# EV75E52A_R3_4-PIC_USB.net
KiCad netlist of a schematic drawn in Altium Designer
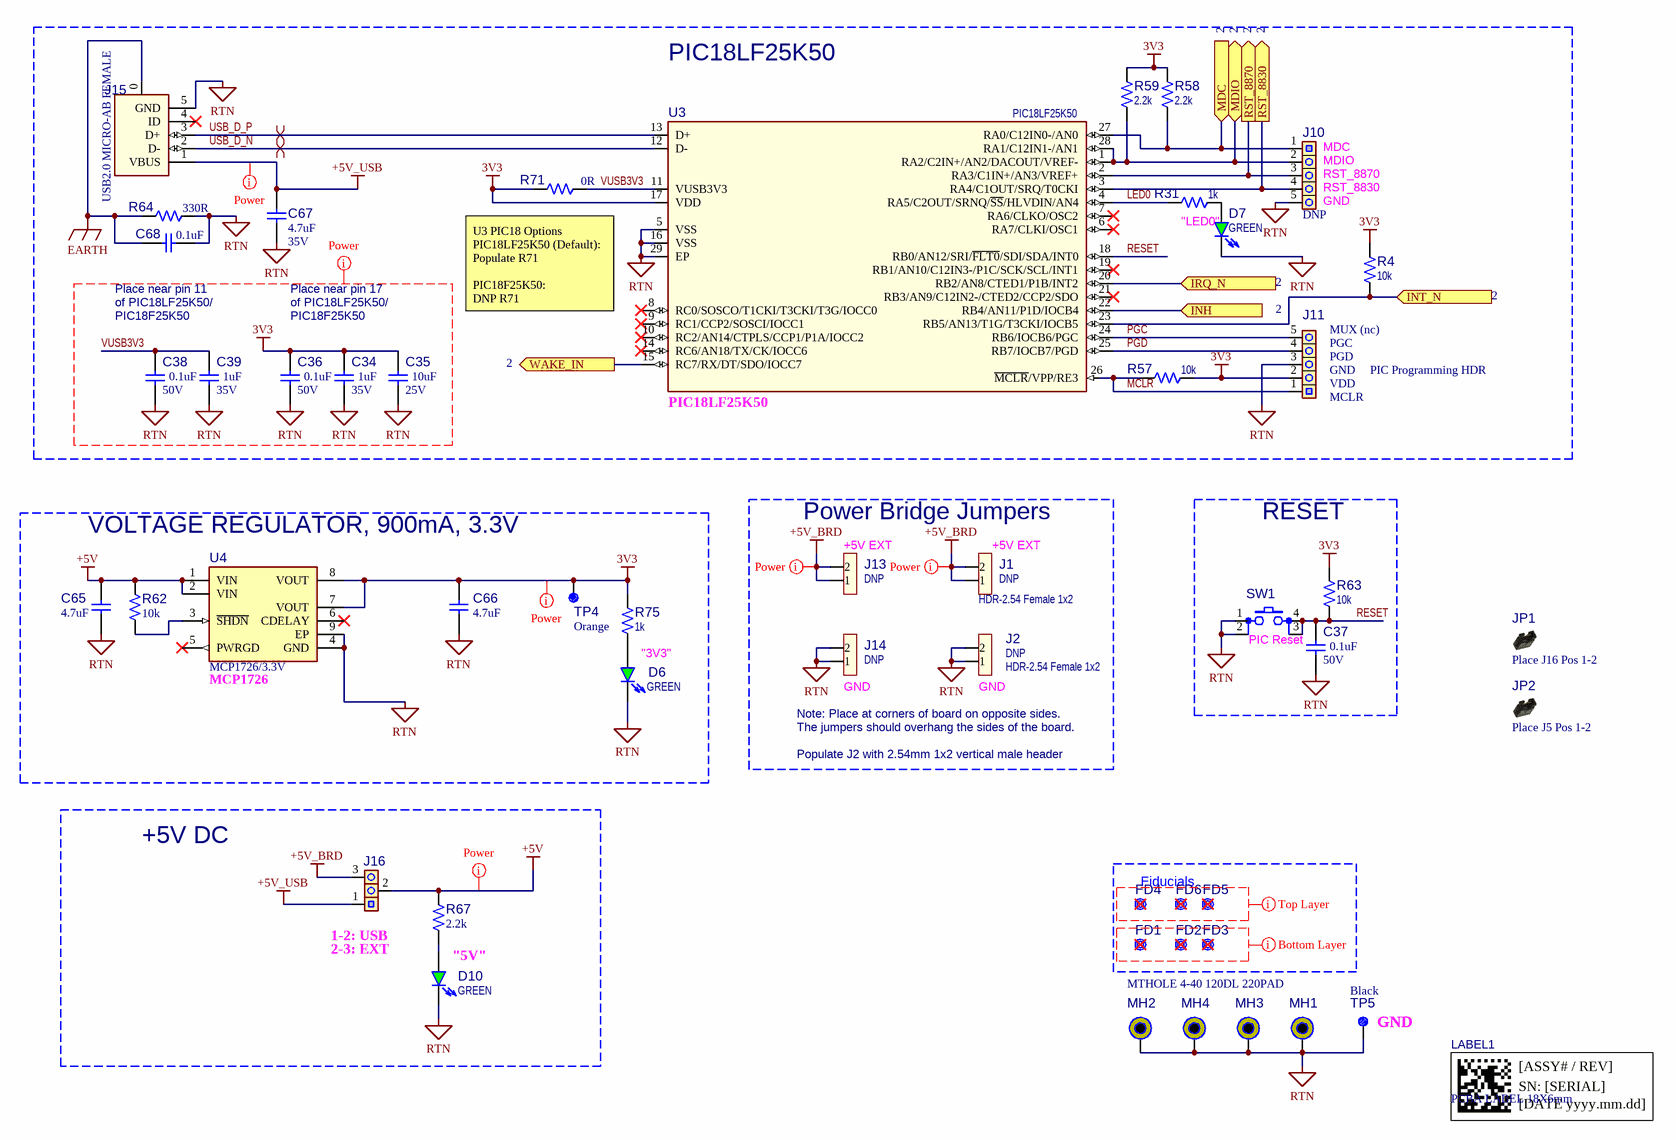
[diagram p0: EV75E52A_R3_4-PIC_USB.SchDoc]

(export (version "E")
  (design (tool "Eeschema 10.0.6"))
  (components
    (comp (ref "C34")
      (value "1uF")
      (footprint "CAP_C_0402")
      (description "Capacitor")
      (fields
        (field (name "VOLTAGE") "35V")
        (field (name "TOLERANCE") "10%")
        (field (name "Comment") "Capacitor NP")
        (field (name "OWNER") "Sam Charles")
      )
      (libsource (lib "MCHP-CDB") (part "Capacitor NP"))
    )
    (comp (ref "C35")
      (value "10uF")
      (footprint "CAP_C_0603")
      (description "Capacitor")
      (fields
        (field (name "VOLTAGE") "25V")
        (field (name "TOLERANCE") "±20%")
        (field (name "Comment") "Capacitor NP")
        (field (name "OWNER") "Tim Moffat")
      )
      (libsource (lib "MCHP-CDB") (part "Capacitor NP"))
    )
    (comp (ref "C36")
      (value "0.1uF")
      (footprint "CAP_C_0402")
      (description "Capacitor")
      (fields
        (field (name "VOLTAGE") "50V")
        (field (name "TOLERANCE") "10%")
        (field (name "Comment") "Capacitor NP")
        (field (name "OWNER") "Jamus Griego")
      )
      (libsource (lib "MCHP-CDB") (part "Capacitor NP"))
    )
    (comp (ref "C37")
      (value "0.1uF")
      (footprint "CAP_C_0402")
      (description "Capacitor")
      (fields
        (field (name "VOLTAGE") "50V")
        (field (name "TOLERANCE") "10%")
        (field (name "Comment") "Capacitor NP")
        (field (name "OWNER") "Jamus Griego")
      )
      (libsource (lib "MCHP-CDB") (part "Capacitor NP"))
    )
    (comp (ref "C38")
      (value "0.1uF")
      (footprint "CAP_C_0402")
      (description "Capacitor")
      (fields
        (field (name "VOLTAGE") "50V")
        (field (name "TOLERANCE") "10%")
        (field (name "Comment") "Capacitor NP")
        (field (name "OWNER") "Jamus Griego")
      )
      (libsource (lib "MCHP-CDB") (part "Capacitor NP"))
    )
    (comp (ref "C39")
      (value "1uF")
      (footprint "CAP_C_0402")
      (description "Capacitor")
      (fields
        (field (name "VOLTAGE") "35V")
        (field (name "TOLERANCE") "10%")
        (field (name "Comment") "Capacitor NP")
        (field (name "OWNER") "Sam Charles")
      )
      (libsource (lib "MCHP-CDB") (part "Capacitor NP"))
    )
    (comp (ref "C65")
      (value "4.7uF")
      (footprint "CAP_C_0402")
      (fields
        (field (name "VOLTAGE") "6.3V")
        (field (name "TOLERANCE") "20%")
        (field (name "Comment") "Capacitor NP")
        (field (name "OWNER") "Tad Ahlvers")
      )
      (libsource (lib "") (part "Capacitor NP_1"))
    )
    (comp (ref "C66")
      (value "4.7uF")
      (footprint "CAP_C_0402")
      (fields
        (field (name "VOLTAGE") "6.3V")
        (field (name "TOLERANCE") "20%")
        (field (name "Comment") "Capacitor NP")
        (field (name "OWNER") "Tad Ahlvers")
      )
      (libsource (lib "") (part "Capacitor NP_1"))
    )
    (comp (ref "C67")
      (value "4.7uF")
      (footprint "CAP_C_0603")
      (description "Capacitor")
      (fields
        (field (name "VOLTAGE") "35V")
        (field (name "TOLERANCE") "10%")
        (field (name "Comment") "Capacitor NP")
        (field (name "OWNER") "Sorin Stanoaia")
      )
      (libsource (lib "MCHP-CDB") (part "Capacitor NP"))
    )
    (comp (ref "C68")
      (value "0.1uF")
      (footprint "CAP_C_0402")
      (description "Capacitor")
      (fields
        (field (name "VOLTAGE") "50V")
        (field (name "TOLERANCE") "10%")
        (field (name "OWNER") "Jamus Griego")
      )
      (libsource (lib "MCHP-CDB") (part "Capacitor NP"))
    )
    (comp (ref "D6")
      (value "GREEN")
      (footprint "LED_0603_GREEN")
      (description "LED")
      (fields
        (field (name "POWER") "75mW")
        (field (name "Comment") "LED_green")
        (field (name "OWNER") "Tad Ahlvers")
      )
      (libsource (lib "MCHP-CDB") (part "LED_green"))
    )
    (comp (ref "D7")
      (value "GREEN")
      (footprint "LED_0603_GREEN")
      (description "LED")
      (fields
        (field (name "POWER") "75mW")
        (field (name "Comment") "LED_green")
        (field (name "OWNER") "Tad Ahlvers")
      )
      (libsource (lib "MCHP-CDB") (part "LED_green"))
    )
    (comp (ref "D10")
      (value "GREEN")
      (footprint "LED_0603_GREEN")
      (description "LED")
      (fields
        (field (name "POWER") "75mW")
        (field (name "LEGEND NOTE") "\"5V\"")
        (field (name "Comment") "LED_green")
        (field (name "OWNER") "Tad Ahlvers")
      )
      (libsource (lib "MCHP-CDB") (part "LED_green"))
    )
    (comp (ref "FD1")
      (value "FIDUCIAL ROUND")
      (footprint "FIDUCIAL_ROUND_1mm")
      (description "Fiducial")
      (fields (field (name "OWNER") "Cristian Papuc"))
      (libsource (lib "MCHP-CDB") (part "FIDUCIAL ROUND"))
    )
    (comp (ref "FD2")
      (value "FIDUCIAL ROUND")
      (footprint "FIDUCIAL_ROUND_1mm")
      (description "Fiducial")
      (fields (field (name "OWNER") "Cristian Papuc"))
      (libsource (lib "MCHP-CDB") (part "FIDUCIAL ROUND"))
    )
    (comp (ref "FD3")
      (value "FIDUCIAL ROUND")
      (footprint "FIDUCIAL_ROUND_1mm")
      (description "Fiducial")
      (fields (field (name "OWNER") "Cristian Papuc"))
      (libsource (lib "MCHP-CDB") (part "FIDUCIAL ROUND"))
    )
    (comp (ref "FD4")
      (value "FIDUCIAL ROUND")
      (footprint "FIDUCIAL_ROUND_1mm")
      (description "Fiducial")
      (fields (field (name "OWNER") "Cristian Papuc"))
      (libsource (lib "MCHP-CDB") (part "FIDUCIAL ROUND"))
    )
    (comp (ref "FD5")
      (value "FIDUCIAL ROUND")
      (footprint "FIDUCIAL_ROUND_1mm")
      (description "Fiducial")
      (fields (field (name "OWNER") "Cristian Papuc"))
      (libsource (lib "MCHP-CDB") (part "FIDUCIAL ROUND"))
    )
    (comp (ref "FD6")
      (value "FIDUCIAL ROUND")
      (footprint "FIDUCIAL_ROUND_1mm")
      (description "Fiducial")
      (fields (field (name "OWNER") "Cristian Papuc"))
      (libsource (lib "MCHP-CDB") (part "FIDUCIAL ROUND"))
    )
    (comp (ref "J1")
      (value "HDR-2.54 Female 1x2")
      (footprint "HDR_F_2.54_1x2_RA")
      (fields
        (field (name "POPULATED") "DNP")
        (field (name "Comment") "Header 1x2")
        (field (name "OWNER") "Jairuz Agang-ang")
      )
      (libsource (lib "MCHP-CDB") (part "Header 1x2"))
    )
    (comp (ref "J2")
      (value "HDR-2.54 Female 1x2")
      (footprint "HDR_F_2.54_1x2_RA")
      (fields
        (field (name "POPULATED") "DNP")
        (field (name "Comment") "Header 1x2")
        (field (name "OWNER") "Jairuz Agang-ang")
      )
      (libsource (lib "MCHP-CDB") (part "Header 1x2"))
    )
    (comp (ref "J10")
      (value "Header 1x5")
      (footprint "HDR_M_2.54_1x5")
      (fields (field (name "POPULATED") "DNP"))
      (libsource (lib "") (part "Header 1x5_1"))
    )
    (comp (ref "J11")
      (value "Header 1x5")
      (footprint "HDR_M_2.54_1x5")
      (libsource (lib "MCHP-CDB") (part "Header 1x5"))
    )
    (comp (ref "J13")
      (value "Header 1x2")
      (footprint "HDR_M_2.54_1x2_RA")
      (fields (field (name "POPULATED") "DNP") (field (name "OWNER") "Jojie Batislaon"))
      (libsource (lib "MCHP-CDB") (part "Header 1x2"))
    )
    (comp (ref "J14")
      (value "Header 1x2")
      (footprint "HDR_M_2.54_1x2_RA")
      (fields (field (name "POPULATED") "DNP") (field (name "OWNER") "Jojie Batislaon"))
      (libsource (lib "MCHP-CDB") (part "Header 1x2"))
    )
    (comp (ref "J15")
      (value "USB2.0 MICRO-AB FEMALE")
      (footprint "CON_USB_Micro-AB_SMD_RA_HIR_ZX62-AB-5PA(11)")
      (description "Connector USB Mini")
      (fields (field (name "Comment") "CON USB2.0 Mini_Micro"))
      (libsource (lib "MCHP-CDB") (part "CON USB2.0 Mini_Micro"))
    )
    (comp (ref "J16")
      (value "Header 1x3")
      (footprint "HDR_M_2.54_1x3")
      (fields (field (name "OWNER") "Bogdan P (M91398)"))
      (libsource (lib "MCHP-CDB") (part "Header 1x3"))
    )
    (comp (ref "JP1")
      (value "Jumper Mechanical")
      (footprint "Jumper_W_Handle_Mechanical")
      (fields (field (name "BOM NOTES") "Place J16 Pos 1-2") (field (name "OWNER") "Jairuz Agang-ang"))
      (libsource (lib "MCHP-CDB") (part "Jumper Mechanical"))
    )
    (comp (ref "JP2")
      (value "Jumper Mechanical")
      (footprint "Jumper_W_Handle_Mechanical")
      (fields (field (name "BOM NOTES") "Place J5 Pos 1-2") (field (name "OWNER") "Jairuz Agang-ang"))
      (libsource (lib "MCHP-CDB") (part "Jumper Mechanical"))
    )
    (comp (ref "LABEL1")
      (value "PCBA LABEL 18X6mm")
      (footprint "08-10015")
      (fields (field (name "Comment") "08-10015"))
      (libsource (lib "MCHP-CDB") (part "08-10015"))
    )
    (comp (ref "MH1")
      (value "~")
      (footprint "MTHOLE_4-40")
      (description "MTHOLE 4-40 120DL 220PAD")
      (libsource (lib "UNG_MISC") (part "MTHOLE 4-40 120DL 220PAD"))
    )
    (comp (ref "MH2")
      (value "~")
      (footprint "MTHOLE_4-40")
      (description "MTHOLE 4-40 120DL 220PAD")
      (libsource (lib "UNG_MISC") (part "MTHOLE 4-40 120DL 220PAD"))
    )
    (comp (ref "MH3")
      (value "~")
      (footprint "MTHOLE_4-40")
      (description "MTHOLE 4-40 120DL 220PAD")
      (libsource (lib "UNG_MISC") (part "MTHOLE 4-40 120DL 220PAD"))
    )
    (comp (ref "MH4")
      (value "~")
      (footprint "MTHOLE_4-40")
      (description "MTHOLE 4-40 120DL 220PAD")
      (fields (field (name "DESCRIPTION_") "MTHOLE 4-40 120DL 220PAD"))
      (libsource (lib "UNG_MISC") (part "MTHOLE 4-40 120DL 220PAD"))
    )
    (comp (ref "R4")
      (value "10k")
      (footprint "RES_C_0402")
      (description "Resistor")
      (fields (field (name "TOLERANCE") "5%") (field (name "VOLTAGE") "50V"))
      (libsource (lib "MCHP-CDB") (part "Resistor"))
    )
    (comp (ref "R31")
      (value "1k")
      (footprint "RES_C_0402")
      (description "Resistor")
      (fields
        (field (name "TOLERANCE") "0.1%")
        (field (name "VOLTAGE") "50V")
        (field (name "OWNER") "Jose Garcia")
      )
      (libsource (lib "MCHP-CDB") (part "Resistor"))
    )
    (comp (ref "R57")
      (value "10k")
      (footprint "RES_C_0402")
      (description "Resistor")
      (fields (field (name "TOLERANCE") "5%") (field (name "VOLTAGE") "50V"))
      (libsource (lib "MCHP-CDB") (part "Resistor"))
    )
    (comp (ref "R58")
      (value "2.2k")
      (footprint "RES_C_0402")
      (description "Resistor")
      (fields
        (field (name "TOLERANCE") "1%")
        (field (name "VOLTAGE") "50V")
        (field (name "OWNER") "Tad Ahlvers")
      )
      (libsource (lib "MCHP-CDB") (part "Resistor"))
    )
    (comp (ref "R59")
      (value "2.2k")
      (footprint "RES_C_0402")
      (description "Resistor")
      (fields
        (field (name "TOLERANCE") "1%")
        (field (name "VOLTAGE") "50V")
        (field (name "OWNER") "Tad Ahlvers")
      )
      (libsource (lib "MCHP-CDB") (part "Resistor"))
    )
    (comp (ref "R62")
      (value "10k")
      (footprint "RES_C_0402")
      (description "Resistor")
      (fields
        (field (name "TOLERANCE") "1%")
        (field (name "VOLTAGE") "50V")
        (field (name "OWNER") "Brent Lanphear")
      )
      (libsource (lib "MCHP-CDB") (part "Resistor"))
    )
    (comp (ref "R63")
      (value "10k")
      (footprint "RES_C_0402")
      (description "Resistor")
      (fields (field (name "TOLERANCE") "5%") (field (name "VOLTAGE") "50V"))
      (libsource (lib "MCHP-CDB") (part "Resistor"))
    )
    (comp (ref "R64")
      (value "330R")
      (footprint "RES_C_0603")
      (description "Resistor")
      (fields (field (name "TOLERANCE") "1%") (field (name "VOLTAGE") "75V"))
      (libsource (lib "MCHP-CDB") (part "Resistor"))
    )
    (comp (ref "R67")
      (value "2.2k")
      (footprint "RES_C_0603")
      (description "Resistor")
      (fields
        (field (name "VOLTAGE") "75V")
        (field (name "POWER") "1/10W")
        (field (name "OWNER") "Bogdan P (M91398)")
      )
      (libsource (lib "MCHP-CDB-Offline") (part "Resistor"))
    )
    (comp (ref "R71")
      (value "0R")
      (footprint "RES_C_0402")
      (description "Resistor")
      (libsource (lib "MCHP-CDB") (part "Resistor"))
    )
    (comp (ref "R75")
      (value "1k")
      (footprint "RES_C_0402")
      (description "Resistor")
      (fields
        (field (name "TOLERANCE") "0.1%")
        (field (name "VOLTAGE") "50V")
        (field (name "OWNER") "Jose Garcia")
      )
      (libsource (lib "MCHP-CDB") (part "Resistor"))
    )
    (comp (ref "SW1")
      (value "Switch 4 Pin")
      (footprint "SW_TACT_SMD_CK_PTS810SJM")
      (description "Switch")
      (fields (field (name "VOLTAGE") "16V") (field (name "OWNER") "Sam Charles"))
      (libsource (lib "MCHP-CDB") (part "Switch 4 Pin"))
    )
    (comp (ref "TP4")
      (value "Orange")
      (footprint "CON_TP_TH_V_ORN_KEC_5003")
      (description "Test Point")
      (fields (field (name "OWNER") "Stephen Humberd"))
      (libsource (lib "MCHP-CDB") (part "Test Point"))
    )
    (comp (ref "TP5")
      (value "Black")
      (footprint "CON_TP_TH_V_BLK_KEC_5001")
      (description "Test Point")
      (fields (field (name "LEGEND NOTES") "GND") (field (name "OWNER") "Stephen Humberd"))
      (libsource (lib "MCHP-CDB") (part "Test Point"))
    )
    (comp (ref "U3")
      (value "PIC18LF25K50")
      (footprint "QFN-28_6X6")
      (fields
        (field (name "LEGEND NOTE") "PIC18LF25K50")
        (field (name "Comment") "PIC18(L)F2XK50 QFN-28")
        (field (name "OWNER") "Jairuz Agang-ang")
      )
      (libsource (lib "MCHP-CDB") (part "PIC18(L)F2XK50 QFN-28"))
    )
    (comp (ref "U4")
      (value "MCP1726/3.3V")
      (footprint "DFN-8_3x3")
      (description "LDO")
      (fields (field (name "LEGEND NOTE") "MCP1726") (field (name "Comment") "MCP1726 FIX DFN-8"))
      (libsource (lib "MCHP-CDB") (part "MCP1726 FIX DFN-8"))
    )
  )
  (nets
    (net (code "1") (name "+5V") (class "Default")
      (node (ref "C65") (pin "2") (pinfunction "2_2") (pintype "passive"))
      (node (ref "J16") (pin "2") (pinfunction "2_2") (pintype "passive"))
      (node (ref "R62") (pin "2") (pinfunction "2_2") (pintype "passive"))
      (node (ref "R67") (pin "1") (pinfunction "1_1") (pintype "passive"))
      (node (ref "U4") (pin "1") (pinfunction "VIN_1") (pintype "power_in"))
      (node (ref "U4") (pin "2") (pinfunction "VIN_2") (pintype "power_in"))
    )
    (net (code "2") (name "+5V_BRD") (class "Default")
      (node (ref "J1") (pin "1") (pinfunction "1_1") (pintype "passive"))
      (node (ref "J1") (pin "2") (pinfunction "2_2") (pintype "passive"))
      (node (ref "J13") (pin "1") (pinfunction "1_1") (pintype "passive"))
      (node (ref "J13") (pin "2") (pinfunction "2_2") (pintype "passive"))
      (node (ref "J16") (pin "3") (pinfunction "3_3") (pintype "passive"))
    )
    (net (code "3") (name "+5V_USB") (class "Default")
      (node (ref "C67") (pin "2") (pinfunction "2_2") (pintype "passive"))
      (node (ref "J15") (pin "1") (pinfunction "VBUS_1") (pintype "power_in"))
      (node (ref "J16") (pin "1") (pinfunction "1_1") (pintype "passive"))
    )
    (net (code "4") (name "/INH") (class "Default")
      (node (ref "U3") (pin "22") (pinfunction "RB4/AN11/P1D/IOCB4_22") (pintype "bidirectional"))
    )
    (net (code "5") (name "/INT_N") (class "Default")
      (node (ref "R4") (pin "2") (pinfunction "2_2") (pintype "passive"))
      (node (ref "U3") (pin "23") (pinfunction "RB5/AN13/T1G/T3CKI/IOCB5_23") (pintype "bidirectional"))
    )
    (net (code "6") (name "/IRQ_N") (class "Default")
      (node (ref "U3") (pin "20") (pinfunction "RB2/AN8/CTED1/P1B/INT2_20") (pintype "bidirectional"))
    )
    (net (code "7") (name "/LED0") (class "Default")
      (node (ref "R31") (pin "2") (pinfunction "2_2") (pintype "passive"))
      (node (ref "U3") (pin "4") (pinfunction "RA5/C2OUT/SRNQ/~{SS}/HLVDIN/AN4_4") (pintype "bidirectional"))
    )
    (net (code "8") (name "/MCLR") (class "Default")
      (node (ref "J11") (pin "1") (pinfunction "P1_1") (pintype "passive"))
      (node (ref "R57") (pin "2") (pinfunction "2_2") (pintype "passive"))
      (node (ref "U3") (pin "26") (pinfunction "~{MCLR}/VPP/RE3_26") (pintype "input"))
    )
    (net (code "9") (name "/MDC") (class "Default")
      (node (ref "J10") (pin "1") (pinfunction "P1_1") (pintype "passive"))
      (node (ref "R58") (pin "1") (pinfunction "1_1") (pintype "passive"))
      (node (ref "U3") (pin "27") (pinfunction "RA0/C12IN0-/AN0_27") (pintype "bidirectional"))
    )
    (net (code "10") (name "/MDIO") (class "Default")
      (node (ref "J10") (pin "2") (pinfunction "P2_2") (pintype "passive"))
      (node (ref "R59") (pin "1") (pinfunction "1_1") (pintype "passive"))
      (node (ref "U3") (pin "1") (pinfunction "RA2/C2IN+/AN2/DACOUT/VREF-_1") (pintype "bidirectional"))
      (node (ref "U3") (pin "28") (pinfunction "RA1/C12IN1-/AN1_28") (pintype "bidirectional"))
    )
    (net (code "11") (name "/PGC") (class "Default")
      (node (ref "J11") (pin "5") (pinfunction "P5_5") (pintype "passive"))
      (node (ref "U3") (pin "24") (pinfunction "RB6/IOCB6/PGC_24") (pintype "bidirectional"))
    )
    (net (code "12") (name "/PGD") (class "Default")
      (node (ref "J11") (pin "4") (pinfunction "P4_4") (pintype "passive"))
      (node (ref "U3") (pin "25") (pinfunction "RB7/IOCB7/PGD_25") (pintype "bidirectional"))
    )
    (net (code "13") (name "/RESET") (class "Default")
      (node (ref "C37") (pin "2") (pinfunction "2_2") (pintype "passive"))
      (node (ref "R63") (pin "2") (pinfunction "2_2") (pintype "passive"))
      (node (ref "SW1") (pin "3") (pinfunction "3_3") (pintype "passive"))
      (node (ref "SW1") (pin "4") (pinfunction "4_4") (pintype "passive"))
      (node (ref "U3") (pin "18") (pinfunction "RB0/AN12/SRI/~{FLT0}/SDI/SDA/INT0_18") (pintype "bidirectional"))
    )
    (net (code "14") (name "/RST_8830") (class "Default")
      (node (ref "J10") (pin "4") (pinfunction "P4_4") (pintype "passive"))
      (node (ref "U3") (pin "3") (pinfunction "RA4/C1OUT/SRQ/T0CKI_3") (pintype "bidirectional"))
    )
    (net (code "15") (name "/RST_8870") (class "Default")
      (node (ref "J10") (pin "3") (pinfunction "P3_3") (pintype "passive"))
      (node (ref "U3") (pin "2") (pinfunction "RA3/C1IN+/AN3/VREF+_2") (pintype "bidirectional"))
    )
    (net (code "16") (name "/USB_D_N") (class "Default")
      (node (ref "J15") (pin "2") (pinfunction "D-_2") (pintype "bidirectional"))
      (node (ref "U3") (pin "12") (pinfunction "D-_12") (pintype "passive"))
    )
    (net (code "17") (name "/USB_D_P") (class "Default")
      (node (ref "J15") (pin "3") (pinfunction "D+_3") (pintype "bidirectional"))
      (node (ref "U3") (pin "13") (pinfunction "D+_13") (pintype "passive"))
    )
    (net (code "18") (name "/VUSB3V3") (class "Default")
      (node (ref "C38") (pin "2") (pinfunction "2_2") (pintype "passive"))
      (node (ref "C39") (pin "2") (pinfunction "2_2") (pintype "passive"))
      (node (ref "R71") (pin "2") (pinfunction "2_2") (pintype "passive"))
      (node (ref "U3") (pin "11") (pinfunction "VUSB3V3_11") (pintype "power_in"))
    )
    (net (code "19") (name "/WAKE_IN") (class "Default")
      (node (ref "U3") (pin "15") (pinfunction "RC7/RX/DT/SDO/IOCC7_15") (pintype "bidirectional"))
    )
    (net (code "20") (name "3V3") (class "Default")
      (node (ref "C34") (pin "2") (pinfunction "2_2") (pintype "passive"))
      (node (ref "C35") (pin "2") (pinfunction "2_2") (pintype "passive"))
      (node (ref "C36") (pin "2") (pinfunction "2_2") (pintype "passive"))
      (node (ref "C66") (pin "2") (pinfunction "2_2") (pintype "passive"))
      (node (ref "J11") (pin "2") (pinfunction "P2_2") (pintype "passive"))
      (node (ref "R4") (pin "1") (pinfunction "1_1") (pintype "passive"))
      (node (ref "R57") (pin "1") (pinfunction "1_1") (pintype "passive"))
      (node (ref "R58") (pin "2") (pinfunction "2_2") (pintype "passive"))
      (node (ref "R59") (pin "2") (pinfunction "2_2") (pintype "passive"))
      (node (ref "R63") (pin "1") (pinfunction "1_1") (pintype "passive"))
      (node (ref "R71") (pin "1") (pinfunction "1_1") (pintype "passive"))
      (node (ref "R75") (pin "2") (pinfunction "2_2") (pintype "passive"))
      (node (ref "TP4") (pin "1") (pinfunction "1_1") (pintype "passive"))
      (node (ref "U3") (pin "17") (pinfunction "VDD_17") (pintype "power_in"))
      (node (ref "U4") (pin "7") (pinfunction "VOUT_7") (pintype "passive"))
      (node (ref "U4") (pin "8") (pinfunction "VOUT_8") (pintype "power_in"))
    )
    (net (code "21") (name "EARTH") (class "Default")
      (node (ref "C68") (pin "2") (pinfunction "2_2") (pintype "passive"))
      (node (ref "J15") (pin "0") (pinfunction "SHLD_0") (pintype "passive"))
      (node (ref "R64") (pin "2") (pinfunction "2_2") (pintype "passive"))
    )
    (net (code "22") (name "Net-(D6-A)") (class "Default")
      (node (ref "D6") (pin "1") (pinfunction "A_1") (pintype "passive"))
      (node (ref "R75") (pin "1") (pinfunction "1_1") (pintype "passive"))
    )
    (net (code "23") (name "Net-(D7-A)") (class "Default")
      (node (ref "D7") (pin "1") (pinfunction "A_1") (pintype "passive"))
      (node (ref "R31") (pin "1") (pinfunction "1_1") (pintype "passive"))
    )
    (net (code "24") (name "Net-(D10-A)") (class "Default")
      (node (ref "D10") (pin "1") (pinfunction "A_1") (pintype "passive"))
      (node (ref "R67") (pin "2") (pinfunction "2_2") (pintype "passive"))
    )
    (net (code "25") (name "Net-(U4-~{SHDN})") (class "Default")
      (node (ref "R62") (pin "1") (pinfunction "1_1") (pintype "passive"))
      (node (ref "U4") (pin "3") (pinfunction "~{SHDN}_3") (pintype "input"))
    )
    (net (code "26") (name "RTN") (class "Default")
      (node (ref "C34") (pin "1") (pinfunction "1_1") (pintype "passive"))
      (node (ref "C35") (pin "1") (pinfunction "1_1") (pintype "passive"))
      (node (ref "C36") (pin "1") (pinfunction "1_1") (pintype "passive"))
      (node (ref "C37") (pin "1") (pinfunction "1_1") (pintype "passive"))
      (node (ref "C38") (pin "1") (pinfunction "1_1") (pintype "passive"))
      (node (ref "C39") (pin "1") (pinfunction "1_1") (pintype "passive"))
      (node (ref "C65") (pin "1") (pinfunction "1_1") (pintype "passive"))
      (node (ref "C66") (pin "1") (pinfunction "1_1") (pintype "passive"))
      (node (ref "C67") (pin "1") (pinfunction "1_1") (pintype "passive"))
      (node (ref "C68") (pin "1") (pinfunction "1_1") (pintype "passive"))
      (node (ref "D10") (pin "2") (pinfunction "K_2") (pintype "passive"))
      (node (ref "D6") (pin "2") (pinfunction "K_2") (pintype "passive"))
      (node (ref "D7") (pin "2") (pinfunction "K_2") (pintype "passive"))
      (node (ref "J10") (pin "5") (pinfunction "P5_5") (pintype "passive"))
      (node (ref "J11") (pin "3") (pinfunction "P3_3") (pintype "passive"))
      (node (ref "J14") (pin "1") (pinfunction "1_1") (pintype "passive"))
      (node (ref "J14") (pin "2") (pinfunction "2_2") (pintype "passive"))
      (node (ref "J15") (pin "5") (pinfunction "GND_5") (pintype "power_in"))
      (node (ref "J2") (pin "1") (pinfunction "1_1") (pintype "passive"))
      (node (ref "J2") (pin "2") (pinfunction "2_2") (pintype "passive"))
      (node (ref "MH1") (pin "1") (pinfunction "1_1") (pintype "passive"))
      (node (ref "MH2") (pin "1") (pinfunction "1_1") (pintype "passive"))
      (node (ref "MH3") (pin "1") (pinfunction "1_1") (pintype "passive"))
      (node (ref "MH4") (pin "1") (pinfunction "1_1") (pintype "passive"))
      (node (ref "R64") (pin "1") (pinfunction "1_1") (pintype "passive"))
      (node (ref "SW1") (pin "1") (pinfunction "1_1") (pintype "passive"))
      (node (ref "SW1") (pin "2") (pinfunction "2_2") (pintype "passive"))
      (node (ref "TP5") (pin "1") (pinfunction "1_1") (pintype "passive"))
      (node (ref "U3") (pin "16") (pinfunction "VSS_16") (pintype "power_in"))
      (node (ref "U3") (pin "29") (pinfunction "EP_29") (pintype "power_in"))
      (node (ref "U3") (pin "5") (pinfunction "VSS_5") (pintype "power_in"))
      (node (ref "U4") (pin "4") (pinfunction "GND_4") (pintype "power_in"))
      (node (ref "U4") (pin "9") (pinfunction "EP_9") (pintype "passive"))
    )
    (net (code "27") (name "unconnected-(FD1-Pad1)") (class "Default")
      (node (ref "FD1") (pin "1") (pinfunction "1_1") (pintype "passive+no_connect"))
    )
    (net (code "28") (name "unconnected-(FD2-Pad1)") (class "Default")
      (node (ref "FD2") (pin "1") (pinfunction "1_1") (pintype "passive+no_connect"))
    )
    (net (code "29") (name "unconnected-(FD3-Pad1)") (class "Default")
      (node (ref "FD3") (pin "1") (pinfunction "1_1") (pintype "passive+no_connect"))
    )
    (net (code "30") (name "unconnected-(FD4-Pad1)") (class "Default")
      (node (ref "FD4") (pin "1") (pinfunction "1_1") (pintype "passive+no_connect"))
    )
    (net (code "31") (name "unconnected-(FD5-Pad1)") (class "Default")
      (node (ref "FD5") (pin "1") (pinfunction "1_1") (pintype "passive+no_connect"))
    )
    (net (code "32") (name "unconnected-(FD6-Pad1)") (class "Default")
      (node (ref "FD6") (pin "1") (pinfunction "1_1") (pintype "passive+no_connect"))
    )
    (net (code "33") (name "unconnected-(J15-ID-Pad4)") (class "Default")
      (node (ref "J15") (pin "4") (pinfunction "ID_4") (pintype "passive+no_connect"))
    )
    (net (code "34") (name "unconnected-(U3-RA6{slash}CLKO{slash}OSC2-Pad7)") (class "Default")
      (node (ref "U3") (pin "7") (pinfunction "RA6/CLKO/OSC2_7") (pintype "bidirectional+no_connect"))
    )
    (net (code "35") (name "unconnected-(U3-RA7{slash}CLKI{slash}OSC1-Pad6)") (class "Default")
      (node (ref "U3") (pin "6") (pinfunction "RA7/CLKI/OSC1_6") (pintype "bidirectional+no_connect"))
    )
    (net (code "36") (name "unconnected-(U3-RB1{slash}AN10{slash}C12IN3-{slash}P1C{slash}SCK{slash}SCL{slash}INT1-Pad19)") (class "Default")
      (node (ref "U3") (pin "19") (pinfunction "RB1/AN10/C12IN3-/P1C/SCK/SCL/INT1_19") (pintype "bidirectional+no_connect"))
    )
    (net (code "37") (name "unconnected-(U3-RB3{slash}AN9{slash}C12IN2-{slash}CTED2{slash}CCP2{slash}SDO-Pad21)") (class "Default")
      (node (ref "U3") (pin "21") (pinfunction "RB3/AN9/C12IN2-/CTED2/CCP2/SDO_21") (pintype "bidirectional+no_connect"))
    )
    (net (code "38") (name "unconnected-(U3-RC0{slash}SOSCO{slash}T1CKI{slash}T3CKI{slash}T3G{slash}IOCC0-Pad8)") (class "Default")
      (node (ref "U3") (pin "8") (pinfunction "RC0/SOSCO/T1CKI/T3CKI/T3G/IOCC0_8") (pintype "bidirectional+no_connect"))
    )
    (net (code "39") (name "unconnected-(U3-RC1{slash}CCP2{slash}SOSCI{slash}IOCC1-Pad9)") (class "Default")
      (node (ref "U3") (pin "9") (pinfunction "RC1/CCP2/SOSCI/IOCC1_9") (pintype "bidirectional+no_connect"))
    )
    (net (code "40") (name "unconnected-(U3-RC2{slash}AN14{slash}CTPLS{slash}CCP1{slash}P1A{slash}IOCC2-Pad10)") (class "Default")
      (node (ref "U3") (pin "10") (pinfunction "RC2/AN14/CTPLS/CCP1/P1A/IOCC2_10") (pintype "bidirectional+no_connect"))
    )
    (net (code "41") (name "unconnected-(U3-RC6{slash}AN18{slash}TX{slash}CK{slash}IOCC6-Pad14)") (class "Default")
      (node (ref "U3") (pin "14") (pinfunction "RC6/AN18/TX/CK/IOCC6_14") (pintype "bidirectional+no_connect"))
    )
    (net (code "42") (name "unconnected-(U4-CDELAY-Pad6)") (class "Default")
      (node (ref "U4") (pin "6") (pinfunction "CDELAY_6") (pintype "passive+no_connect"))
    )
    (net (code "43") (name "unconnected-(U4-PWRGD-Pad5)") (class "Default")
      (node (ref "U4") (pin "5") (pinfunction "PWRGD_5") (pintype "output+no_connect"))
    )
  )
)
